# Sheet1.net
KiCad netlist of a schematic drawn in Altium Designer
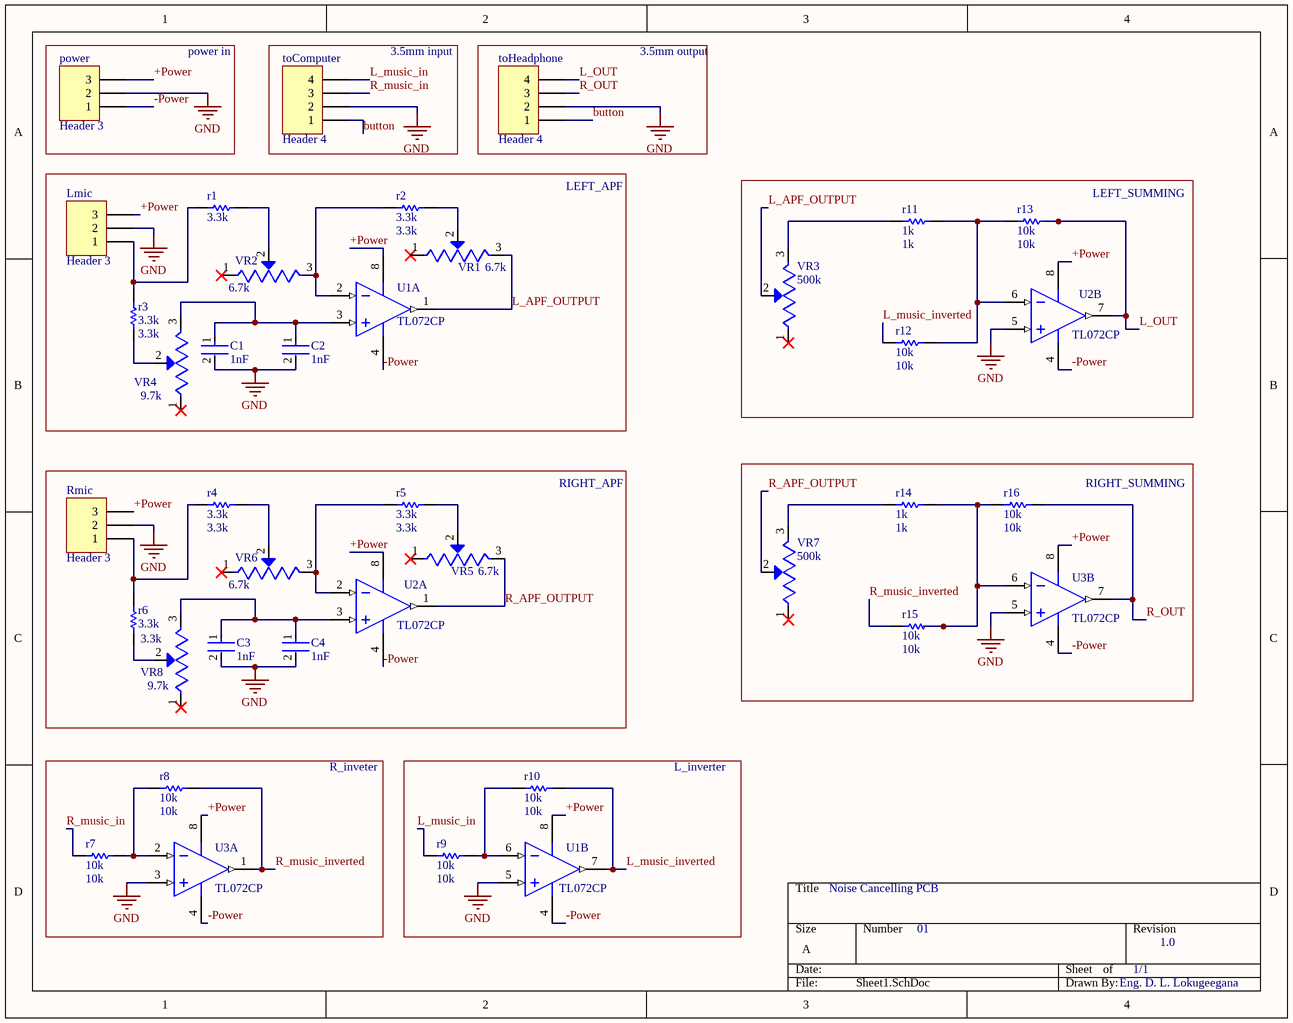
[diagram p0: Sheet1.SchDoc]

(export (version "E")
  (design (tool "Eeschema 10.0.6"))
  (components
    (comp (ref "C1")
      (value "1nF")
      (footprint "FP-RCE3M1-MFG")
      (description "Cap Ceramic 10uF 25V X7R ±10% Radial 5mm +125°C Automotive Ammo Pack")
      (fields (field (name "TOLERANCE") "10%"))
      (libsource (lib "Altium Content Vault") (part "02cd4be3c70576c341d710602a673aa"))
    )
    (comp (ref "C2")
      (value "1nF")
      (footprint "FP-RCE3M1-MFG")
      (description "Cap Ceramic 10uF 25V X7R ±10% Radial 5mm +125°C Automotive Ammo Pack")
      (fields (field (name "TOLERANCE") "10%"))
      (libsource (lib "Altium Content Vault") (part "02cd4be3c70576c341d710602a673aa"))
    )
    (comp (ref "C3")
      (value "1nF")
      (footprint "FP-RCE3M1-MFG")
      (description "Cap Ceramic 10uF 25V X7R ±10% Radial 5mm +125°C Automotive Ammo Pack")
      (fields (field (name "TOLERANCE") "10%"))
      (libsource (lib "Altium Content Vault") (part "02cd4be3c70576c341d710602a673aa"))
    )
    (comp (ref "C4")
      (value "1nF")
      (footprint "FP-RCE3M1-MFG")
      (description "Cap Ceramic 10uF 25V X7R ±10% Radial 5mm +125°C Automotive Ammo Pack")
      (fields (field (name "TOLERANCE") "10%"))
      (libsource (lib "Altium Content Vault") (part "02cd4be3c70576c341d710602a673aa"))
    )
    (comp (ref "Lmic")
      (value "Header 3")
      (footprint "HDR1X3")
      (description "Header, 3-Pin")
      (fields (field (name "PUBLISHER") "Altium Limited"))
      (libsource (lib "Miscellaneous Connectors") (part "Header 3"))
    )
    (comp (ref "power")
      (value "Header 3")
      (footprint "HDR1X3")
      (description "Header, 3-Pin")
      (fields (field (name "PUBLISHER") "Altium Limited"))
      (libsource (lib "Miscellaneous Connectors") (part "Header 3"))
    )
    (comp (ref "r1")
      (value "3.3k")
      (footprint "AXIAL-0.3")
      (description "Resistor")
      (fields (field (name "PUBLISHER") "Altium Limited"))
      (libsource (lib "Miscellaneous Devices") (part "Res1"))
    )
    (comp (ref "r2")
      (value "3.3k")
      (footprint "AXIAL-0.3")
      (description "Resistor")
      (fields (field (name "ALTIUM_VALUE") "3.3k") (field (name "PUBLISHER") "Altium Limited"))
      (libsource (lib "Miscellaneous Devices") (part "Res1"))
    )
    (comp (ref "r3")
      (value "3.3k")
      (footprint "AXIAL-0.3")
      (description "Resistor")
      (fields (field (name "ALTIUM_VALUE") "3.3k") (field (name "PUBLISHER") "Altium Limited"))
      (libsource (lib "Miscellaneous Devices") (part "Res1"))
    )
    (comp (ref "r4")
      (value "3.3k")
      (footprint "AXIAL-0.3")
      (description "Resistor")
      (fields (field (name "ALTIUM_VALUE") "3.3k") (field (name "PUBLISHER") "Altium Limited"))
      (libsource (lib "Miscellaneous Devices") (part "Res1"))
    )
    (comp (ref "r5")
      (value "3.3k")
      (footprint "AXIAL-0.3")
      (description "Resistor")
      (fields (field (name "ALTIUM_VALUE") "3.3k") (field (name "PUBLISHER") "Altium Limited"))
      (libsource (lib "Miscellaneous Devices") (part "Res1"))
    )
    (comp (ref "r6")
      (value "3.3k")
      (footprint "AXIAL-0.3")
      (description "Resistor")
      (fields (field (name "ALTIUM_VALUE") "3.3k") (field (name "PUBLISHER") "Altium Limited"))
      (libsource (lib "Miscellaneous Devices") (part "Res1"))
    )
    (comp (ref "r7")
      (value "10k")
      (footprint "AXIAL-0.3")
      (description "Resistor")
      (fields (field (name "ALTIUM_VALUE") "10k") (field (name "PUBLISHER") "Altium Limited"))
      (libsource (lib "Miscellaneous Devices") (part "Res1"))
    )
    (comp (ref "r8")
      (value "10k")
      (footprint "AXIAL-0.3")
      (description "Resistor")
      (fields (field (name "ALTIUM_VALUE") "10k") (field (name "PUBLISHER") "Altium Limited"))
      (libsource (lib "Miscellaneous Devices") (part "Res1"))
    )
    (comp (ref "r9")
      (value "10k")
      (footprint "AXIAL-0.3")
      (description "Resistor")
      (fields (field (name "ALTIUM_VALUE") "10k") (field (name "PUBLISHER") "Altium Limited"))
      (libsource (lib "Miscellaneous Devices") (part "Res1"))
    )
    (comp (ref "r10")
      (value "10k")
      (footprint "AXIAL-0.3")
      (description "Resistor")
      (fields (field (name "ALTIUM_VALUE") "10k") (field (name "PUBLISHER") "Altium Limited"))
      (libsource (lib "Miscellaneous Devices") (part "Res1"))
    )
    (comp (ref "r11")
      (value "1k")
      (footprint "AXIAL-0.3")
      (description "Resistor")
      (fields (field (name "ALTIUM_VALUE") "1k") (field (name "PUBLISHER") "Altium Limited"))
      (libsource (lib "Miscellaneous Devices") (part "Res1"))
    )
    (comp (ref "r12")
      (value "10k")
      (footprint "AXIAL-0.3")
      (description "Resistor")
      (fields (field (name "ALTIUM_VALUE") "10k") (field (name "PUBLISHER") "Altium Limited"))
      (libsource (lib "Miscellaneous Devices") (part "Res1"))
    )
    (comp (ref "r13")
      (value "10k")
      (footprint "AXIAL-0.3")
      (description "Resistor")
      (fields (field (name "ALTIUM_VALUE") "10k") (field (name "PUBLISHER") "Altium Limited"))
      (libsource (lib "Miscellaneous Devices") (part "Res1"))
    )
    (comp (ref "r14")
      (value "1k")
      (footprint "AXIAL-0.3")
      (description "Resistor")
      (fields (field (name "ALTIUM_VALUE") "1k") (field (name "PUBLISHER") "Altium Limited"))
      (libsource (lib "Miscellaneous Devices") (part "Res1"))
    )
    (comp (ref "r15")
      (value "10k")
      (footprint "AXIAL-0.3")
      (description "Resistor")
      (fields (field (name "ALTIUM_VALUE") "10k") (field (name "PUBLISHER") "Altium Limited"))
      (libsource (lib "Miscellaneous Devices") (part "Res1"))
    )
    (comp (ref "r16")
      (value "10k")
      (footprint "AXIAL-0.3")
      (description "Resistor")
      (fields (field (name "ALTIUM_VALUE") "10k") (field (name "PUBLISHER") "Altium Limited"))
      (libsource (lib "Miscellaneous Devices") (part "Res1"))
    )
    (comp (ref "Rmic")
      (value "Header 3")
      (footprint "HDR1X3")
      (description "Header, 3-Pin")
      (fields (field (name "PUBLISHER") "Altium Limited"))
      (libsource (lib "Miscellaneous Connectors") (part "Header 3"))
    )
    (comp (ref "toComputer")
      (value "Header 4")
      (footprint "HDR1X4")
      (description "Header, 4-Pin")
      (fields (field (name "PUBLISHER") "Altium Limited"))
      (libsource (lib "Miscellaneous Connectors") (part "Header 4"))
    )
    (comp (ref "toHeadphone")
      (value "Header 4")
      (footprint "HDR1X4")
      (description "Header, 4-Pin")
      (fields (field (name "PUBLISHER") "Altium Limited"))
      (libsource (lib "Miscellaneous Connectors") (part "Header 4"))
    )
    (comp (ref "U1")
      (value "TL072CP")
      (footprint "P0008A")
      (fields (field (name "MANUFACTURER") "Texas Instruments"))
      (libsource (lib "Altium Content Vault") (part "TI-AMP-D6-2-8_D"))
    )
    (comp (ref "U2")
      (value "TL072CP")
      (footprint "P0008A")
      (fields (field (name "MANUFACTURER") "Texas Instruments"))
      (libsource (lib "Altium Content Vault") (part "TI-AMP-D6-2-8_D"))
    )
    (comp (ref "U3")
      (value "TL072CP")
      (footprint "P0008A")
      (fields (field (name "MANUFACTURER") "Texas Instruments"))
      (libsource (lib "Altium Content Vault") (part "TI-AMP-D6-2-8_D"))
    )
    (comp (ref "VR1")
      (value "6.7k")
      (footprint "TRIM_3296W-1-250")
      (description "25 Ohms 0.5W, 1/2W PC Pins Through Hole Trimmer Potentiometer Cermet 25.0 Turn Top Adjustment")
      (fields (field (name "MF") "Bourns") (field (name "MP") "3296W-1-250"))
      (libsource (lib "Schlib1") (part "3296W-1-250"))
    )
    (comp (ref "VR2")
      (value "6.7k")
      (footprint "TRIM_3296W-1-250")
      (description "25 Ohms 0.5W, 1/2W PC Pins Through Hole Trimmer Potentiometer Cermet 25.0 Turn Top Adjustment")
      (fields (field (name "MF") "Bourns") (field (name "MP") "3296W-1-250"))
      (libsource (lib "Schlib1") (part "3296W-1-250"))
    )
    (comp (ref "VR3")
      (value "500k")
      (footprint "TRIM_3296W-1-250")
      (description "25 Ohms 0.5W, 1/2W PC Pins Through Hole Trimmer Potentiometer Cermet 25.0 Turn Top Adjustment")
      (fields (field (name "MF") "Bourns") (field (name "MP") "3296W-1-250"))
      (libsource (lib "Schlib1") (part "3296W-1-250"))
    )
    (comp (ref "VR4")
      (value "9.7k")
      (footprint "TRIM_3296W-1-250")
      (description "25 Ohms 0.5W, 1/2W PC Pins Through Hole Trimmer Potentiometer Cermet 25.0 Turn Top Adjustment")
      (fields (field (name "MF") "Bourns") (field (name "MP") "3296W-1-250"))
      (libsource (lib "Schlib1") (part "3296W-1-250"))
    )
    (comp (ref "VR5")
      (value "6.7k")
      (footprint "TRIM_3296W-1-250")
      (description "25 Ohms 0.5W, 1/2W PC Pins Through Hole Trimmer Potentiometer Cermet 25.0 Turn Top Adjustment")
      (fields (field (name "MF") "Bourns") (field (name "MP") "3296W-1-250"))
      (libsource (lib "Schlib1") (part "3296W-1-250"))
    )
    (comp (ref "VR6")
      (value "6.7k")
      (footprint "TRIM_3296W-1-250")
      (description "25 Ohms 0.5W, 1/2W PC Pins Through Hole Trimmer Potentiometer Cermet 25.0 Turn Top Adjustment")
      (fields (field (name "MF") "Bourns") (field (name "MP") "3296W-1-250"))
      (libsource (lib "Schlib1") (part "3296W-1-250"))
    )
    (comp (ref "VR7")
      (value "500k")
      (footprint "TRIM_3296W-1-250")
      (description "25 Ohms 0.5W, 1/2W PC Pins Through Hole Trimmer Potentiometer Cermet 25.0 Turn Top Adjustment")
      (fields (field (name "MF") "Bourns") (field (name "MP") "3296W-1-250"))
      (libsource (lib "Schlib1") (part "3296W-1-250"))
    )
    (comp (ref "VR8")
      (value "9.7k")
      (footprint "TRIM_3296W-1-250")
      (description "25 Ohms 0.5W, 1/2W PC Pins Through Hole Trimmer Potentiometer Cermet 25.0 Turn Top Adjustment")
      (fields (field (name "MF") "Bourns") (field (name "MP") "3296W-1-250"))
      (libsource (lib "Schlib1") (part "3296W-1-250"))
    )
  )
  (nets
    (net (code "1") (name "/+Power") (class "Default")
      (node (ref "Lmic") (pin "3") (pinfunction "3_3") (pintype "passive"))
      (node (ref "Rmic") (pin "3") (pinfunction "3_3") (pintype "passive"))
      (node (ref "U1") (pin "8") (pinfunction "VCC+_8") (pintype "power_in"))
      (node (ref "U2") (pin "8") (pinfunction "VCC+_8") (pintype "power_in"))
      (node (ref "U3") (pin "8") (pinfunction "VCC+_8") (pintype "power_in"))
      (node (ref "power") (pin "3") (pinfunction "3_3") (pintype "passive"))
    )
    (net (code "2") (name "/-Power") (class "Default")
      (node (ref "U1") (pin "4") (pinfunction "VCC-_4") (pintype "power_in"))
      (node (ref "U2") (pin "4") (pinfunction "VCC-_4") (pintype "power_in"))
      (node (ref "U3") (pin "4") (pinfunction "VCC-_4") (pintype "power_in"))
      (node (ref "power") (pin "1") (pinfunction "1_1") (pintype "passive"))
    )
    (net (code "3") (name "/L_APF_OUTPUT") (class "Default")
      (node (ref "U1") (pin "1") (pinfunction "OUT1_1") (pintype "output"))
      (node (ref "VR1") (pin "3") (pinfunction "CW_3") (pintype "passive"))
      (node (ref "VR3") (pin "2") (pinfunction "WIPER_2") (pintype "passive"))
    )
    (net (code "4") (name "/L_OUT") (class "Default")
      (node (ref "U2") (pin "7") (pinfunction "OUT2_7") (pintype "output"))
      (node (ref "r13") (pin "2") (pinfunction "2_2") (pintype "passive"))
      (node (ref "toHeadphone") (pin "4") (pinfunction "4_4") (pintype "passive"))
    )
    (net (code "5") (name "/L_music_in") (class "Default")
      (node (ref "r9") (pin "1") (pinfunction "1_1") (pintype "passive"))
      (node (ref "toComputer") (pin "4") (pinfunction "4_4") (pintype "passive"))
    )
    (net (code "6") (name "/L_music_inverted") (class "Default")
      (node (ref "U1") (pin "7") (pinfunction "OUT2_7") (pintype "output"))
      (node (ref "r10") (pin "2") (pinfunction "2_2") (pintype "passive"))
      (node (ref "r12") (pin "1") (pinfunction "1_1") (pintype "passive"))
    )
    (net (code "7") (name "/R_APF_OUTPUT") (class "Default")
      (node (ref "U2") (pin "1") (pinfunction "OUT1_1") (pintype "output"))
      (node (ref "VR5") (pin "3") (pinfunction "CW_3") (pintype "passive"))
      (node (ref "VR7") (pin "2") (pinfunction "WIPER_2") (pintype "passive"))
    )
    (net (code "8") (name "/R_OUT") (class "Default")
      (node (ref "U3") (pin "7") (pinfunction "OUT2_7") (pintype "output"))
      (node (ref "r16") (pin "2") (pinfunction "2_2") (pintype "passive"))
      (node (ref "toHeadphone") (pin "3") (pinfunction "3_3") (pintype "passive"))
    )
    (net (code "9") (name "/R_music_in") (class "Default")
      (node (ref "r7") (pin "1") (pinfunction "1_1") (pintype "passive"))
      (node (ref "toComputer") (pin "3") (pinfunction "3_3") (pintype "passive"))
    )
    (net (code "10") (name "/R_music_inverted") (class "Default")
      (node (ref "U3") (pin "1") (pinfunction "OUT1_1") (pintype "output"))
      (node (ref "r15") (pin "1") (pinfunction "1_1") (pintype "passive"))
      (node (ref "r8") (pin "2") (pinfunction "2_2") (pintype "passive"))
    )
    (net (code "11") (name "/button") (class "Default")
      (node (ref "toComputer") (pin "1") (pinfunction "1_1") (pintype "passive"))
      (node (ref "toHeadphone") (pin "1") (pinfunction "1_1") (pintype "passive"))
    )
    (net (code "12") (name "GND") (class "Default")
      (node (ref "C1") (pin "2") (pinfunction "2_2") (pintype "passive"))
      (node (ref "C2") (pin "2") (pinfunction "2_2") (pintype "passive"))
      (node (ref "C3") (pin "2") (pinfunction "2_2") (pintype "passive"))
      (node (ref "C4") (pin "2") (pinfunction "2_2") (pintype "passive"))
      (node (ref "Lmic") (pin "2") (pinfunction "2_2") (pintype "passive"))
      (node (ref "Rmic") (pin "2") (pinfunction "2_2") (pintype "passive"))
      (node (ref "U1") (pin "5") (pinfunction "IN2+_5") (pintype "input"))
      (node (ref "U2") (pin "5") (pinfunction "IN2+_5") (pintype "input"))
      (node (ref "U3") (pin "3") (pinfunction "IN1+_3") (pintype "input"))
      (node (ref "U3") (pin "5") (pinfunction "IN2+_5") (pintype "input"))
      (node (ref "power") (pin "2") (pinfunction "2_2") (pintype "passive"))
      (node (ref "toComputer") (pin "2") (pinfunction "2_2") (pintype "passive"))
      (node (ref "toHeadphone") (pin "2") (pinfunction "2_2") (pintype "passive"))
    )
    (net (code "13") (name "Net-(Lmic-Pad1)") (class "Default")
      (node (ref "Lmic") (pin "1") (pinfunction "1_1") (pintype "passive"))
      (node (ref "r1") (pin "1") (pinfunction "1_1") (pintype "passive"))
      (node (ref "r3") (pin "1") (pinfunction "1_1") (pintype "passive"))
    )
    (net (code "14") (name "Net-(Rmic-Pad1)") (class "Default")
      (node (ref "Rmic") (pin "1") (pinfunction "1_1") (pintype "passive"))
      (node (ref "r4") (pin "1") (pinfunction "1_1") (pintype "passive"))
      (node (ref "r6") (pin "2") (pinfunction "2_2") (pintype "passive"))
    )
    (net (code "15") (name "Net-(U1A-IN1+)") (class "Default")
      (node (ref "C1") (pin "1") (pinfunction "1_1") (pintype "passive"))
      (node (ref "C2") (pin "1") (pinfunction "1_1") (pintype "passive"))
      (node (ref "U1") (pin "3") (pinfunction "IN1+_3") (pintype "input"))
      (node (ref "VR4") (pin "3") (pinfunction "CW_3") (pintype "passive"))
    )
    (net (code "16") (name "Net-(U1A-IN1-)") (class "Default")
      (node (ref "U1") (pin "2") (pinfunction "IN1-_2") (pintype "input"))
      (node (ref "VR2") (pin "3") (pinfunction "CW_3") (pintype "passive"))
      (node (ref "r2") (pin "1") (pinfunction "1_1") (pintype "passive"))
    )
    (net (code "17") (name "Net-(U1B-IN2-)") (class "Default")
      (node (ref "U1") (pin "6") (pinfunction "IN2-_6") (pintype "input"))
      (node (ref "r10") (pin "1") (pinfunction "1_1") (pintype "passive"))
      (node (ref "r9") (pin "2") (pinfunction "2_2") (pintype "passive"))
    )
    (net (code "18") (name "Net-(U2A-IN1+)") (class "Default")
      (node (ref "C3") (pin "1") (pinfunction "1_1") (pintype "passive"))
      (node (ref "C4") (pin "1") (pinfunction "1_1") (pintype "passive"))
      (node (ref "U2") (pin "3") (pinfunction "IN1+_3") (pintype "input"))
      (node (ref "VR8") (pin "3") (pinfunction "CW_3") (pintype "passive"))
    )
    (net (code "19") (name "Net-(U2A-IN1-)") (class "Default")
      (node (ref "U2") (pin "2") (pinfunction "IN1-_2") (pintype "input"))
      (node (ref "VR6") (pin "3") (pinfunction "CW_3") (pintype "passive"))
      (node (ref "r5") (pin "1") (pinfunction "1_1") (pintype "passive"))
    )
    (net (code "20") (name "Net-(U2B-IN2-)") (class "Default")
      (node (ref "U2") (pin "6") (pinfunction "IN2-_6") (pintype "input"))
      (node (ref "r11") (pin "2") (pinfunction "2_2") (pintype "passive"))
      (node (ref "r12") (pin "2") (pinfunction "2_2") (pintype "passive"))
      (node (ref "r13") (pin "1") (pinfunction "1_1") (pintype "passive"))
    )
    (net (code "21") (name "Net-(U3A-IN1-)") (class "Default")
      (node (ref "U3") (pin "2") (pinfunction "IN1-_2") (pintype "input"))
      (node (ref "r7") (pin "2") (pinfunction "2_2") (pintype "passive"))
      (node (ref "r8") (pin "1") (pinfunction "1_1") (pintype "passive"))
    )
    (net (code "22") (name "Net-(U3B-IN2-)") (class "Default")
      (node (ref "U3") (pin "6") (pinfunction "IN2-_6") (pintype "input"))
      (node (ref "r14") (pin "2") (pinfunction "2_2") (pintype "passive"))
      (node (ref "r15") (pin "2") (pinfunction "2_2") (pintype "passive"))
      (node (ref "r16") (pin "1") (pinfunction "1_1") (pintype "passive"))
    )
    (net (code "23") (name "Net-(VR1-WIPER)") (class "Default")
      (node (ref "VR1") (pin "2") (pinfunction "WIPER_2") (pintype "passive"))
      (node (ref "r2") (pin "2") (pinfunction "2_2") (pintype "passive"))
    )
    (net (code "24") (name "Net-(VR2-WIPER)") (class "Default")
      (node (ref "VR2") (pin "2") (pinfunction "WIPER_2") (pintype "passive"))
      (node (ref "r1") (pin "2") (pinfunction "2_2") (pintype "passive"))
    )
    (net (code "25") (name "Net-(VR3-CW)") (class "Default")
      (node (ref "VR3") (pin "3") (pinfunction "CW_3") (pintype "passive"))
      (node (ref "r11") (pin "1") (pinfunction "1_1") (pintype "passive"))
    )
    (net (code "26") (name "Net-(VR4-WIPER)") (class "Default")
      (node (ref "VR4") (pin "2") (pinfunction "WIPER_2") (pintype "passive"))
      (node (ref "r3") (pin "2") (pinfunction "2_2") (pintype "passive"))
    )
    (net (code "27") (name "Net-(VR5-WIPER)") (class "Default")
      (node (ref "VR5") (pin "2") (pinfunction "WIPER_2") (pintype "passive"))
      (node (ref "r5") (pin "2") (pinfunction "2_2") (pintype "passive"))
    )
    (net (code "28") (name "Net-(VR6-WIPER)") (class "Default")
      (node (ref "VR6") (pin "2") (pinfunction "WIPER_2") (pintype "passive"))
      (node (ref "r4") (pin "2") (pinfunction "2_2") (pintype "passive"))
    )
    (net (code "29") (name "Net-(VR7-CW)") (class "Default")
      (node (ref "VR7") (pin "3") (pinfunction "CW_3") (pintype "passive"))
      (node (ref "r14") (pin "1") (pinfunction "1_1") (pintype "passive"))
    )
    (net (code "30") (name "Net-(VR8-WIPER)") (class "Default")
      (node (ref "VR8") (pin "2") (pinfunction "WIPER_2") (pintype "passive"))
      (node (ref "r6") (pin "1") (pinfunction "1_1") (pintype "passive"))
    )
    (net (code "31") (name "unconnected-(VR1-CCW-Pad1)") (class "Default")
      (node (ref "VR1") (pin "1") (pinfunction "CCW_1") (pintype "passive+no_connect"))
    )
    (net (code "32") (name "unconnected-(VR2-CCW-Pad1)") (class "Default")
      (node (ref "VR2") (pin "1") (pinfunction "CCW_1") (pintype "passive+no_connect"))
    )
    (net (code "33") (name "unconnected-(VR3-CCW-Pad1)") (class "Default")
      (node (ref "VR3") (pin "1") (pinfunction "CCW_1") (pintype "passive+no_connect"))
    )
    (net (code "34") (name "unconnected-(VR4-CCW-Pad1)") (class "Default")
      (node (ref "VR4") (pin "1") (pinfunction "CCW_1") (pintype "passive+no_connect"))
    )
    (net (code "35") (name "unconnected-(VR5-CCW-Pad1)") (class "Default")
      (node (ref "VR5") (pin "1") (pinfunction "CCW_1") (pintype "passive+no_connect"))
    )
    (net (code "36") (name "unconnected-(VR6-CCW-Pad1)") (class "Default")
      (node (ref "VR6") (pin "1") (pinfunction "CCW_1") (pintype "passive+no_connect"))
    )
    (net (code "37") (name "unconnected-(VR7-CCW-Pad1)") (class "Default")
      (node (ref "VR7") (pin "1") (pinfunction "CCW_1") (pintype "passive+no_connect"))
    )
    (net (code "38") (name "unconnected-(VR8-CCW-Pad1)") (class "Default")
      (node (ref "VR8") (pin "1") (pinfunction "CCW_1") (pintype "passive+no_connect"))
    )
  )
)
